# Grupa2_sema.net
KiCad netlist of a schematic drawn in Altium Designer
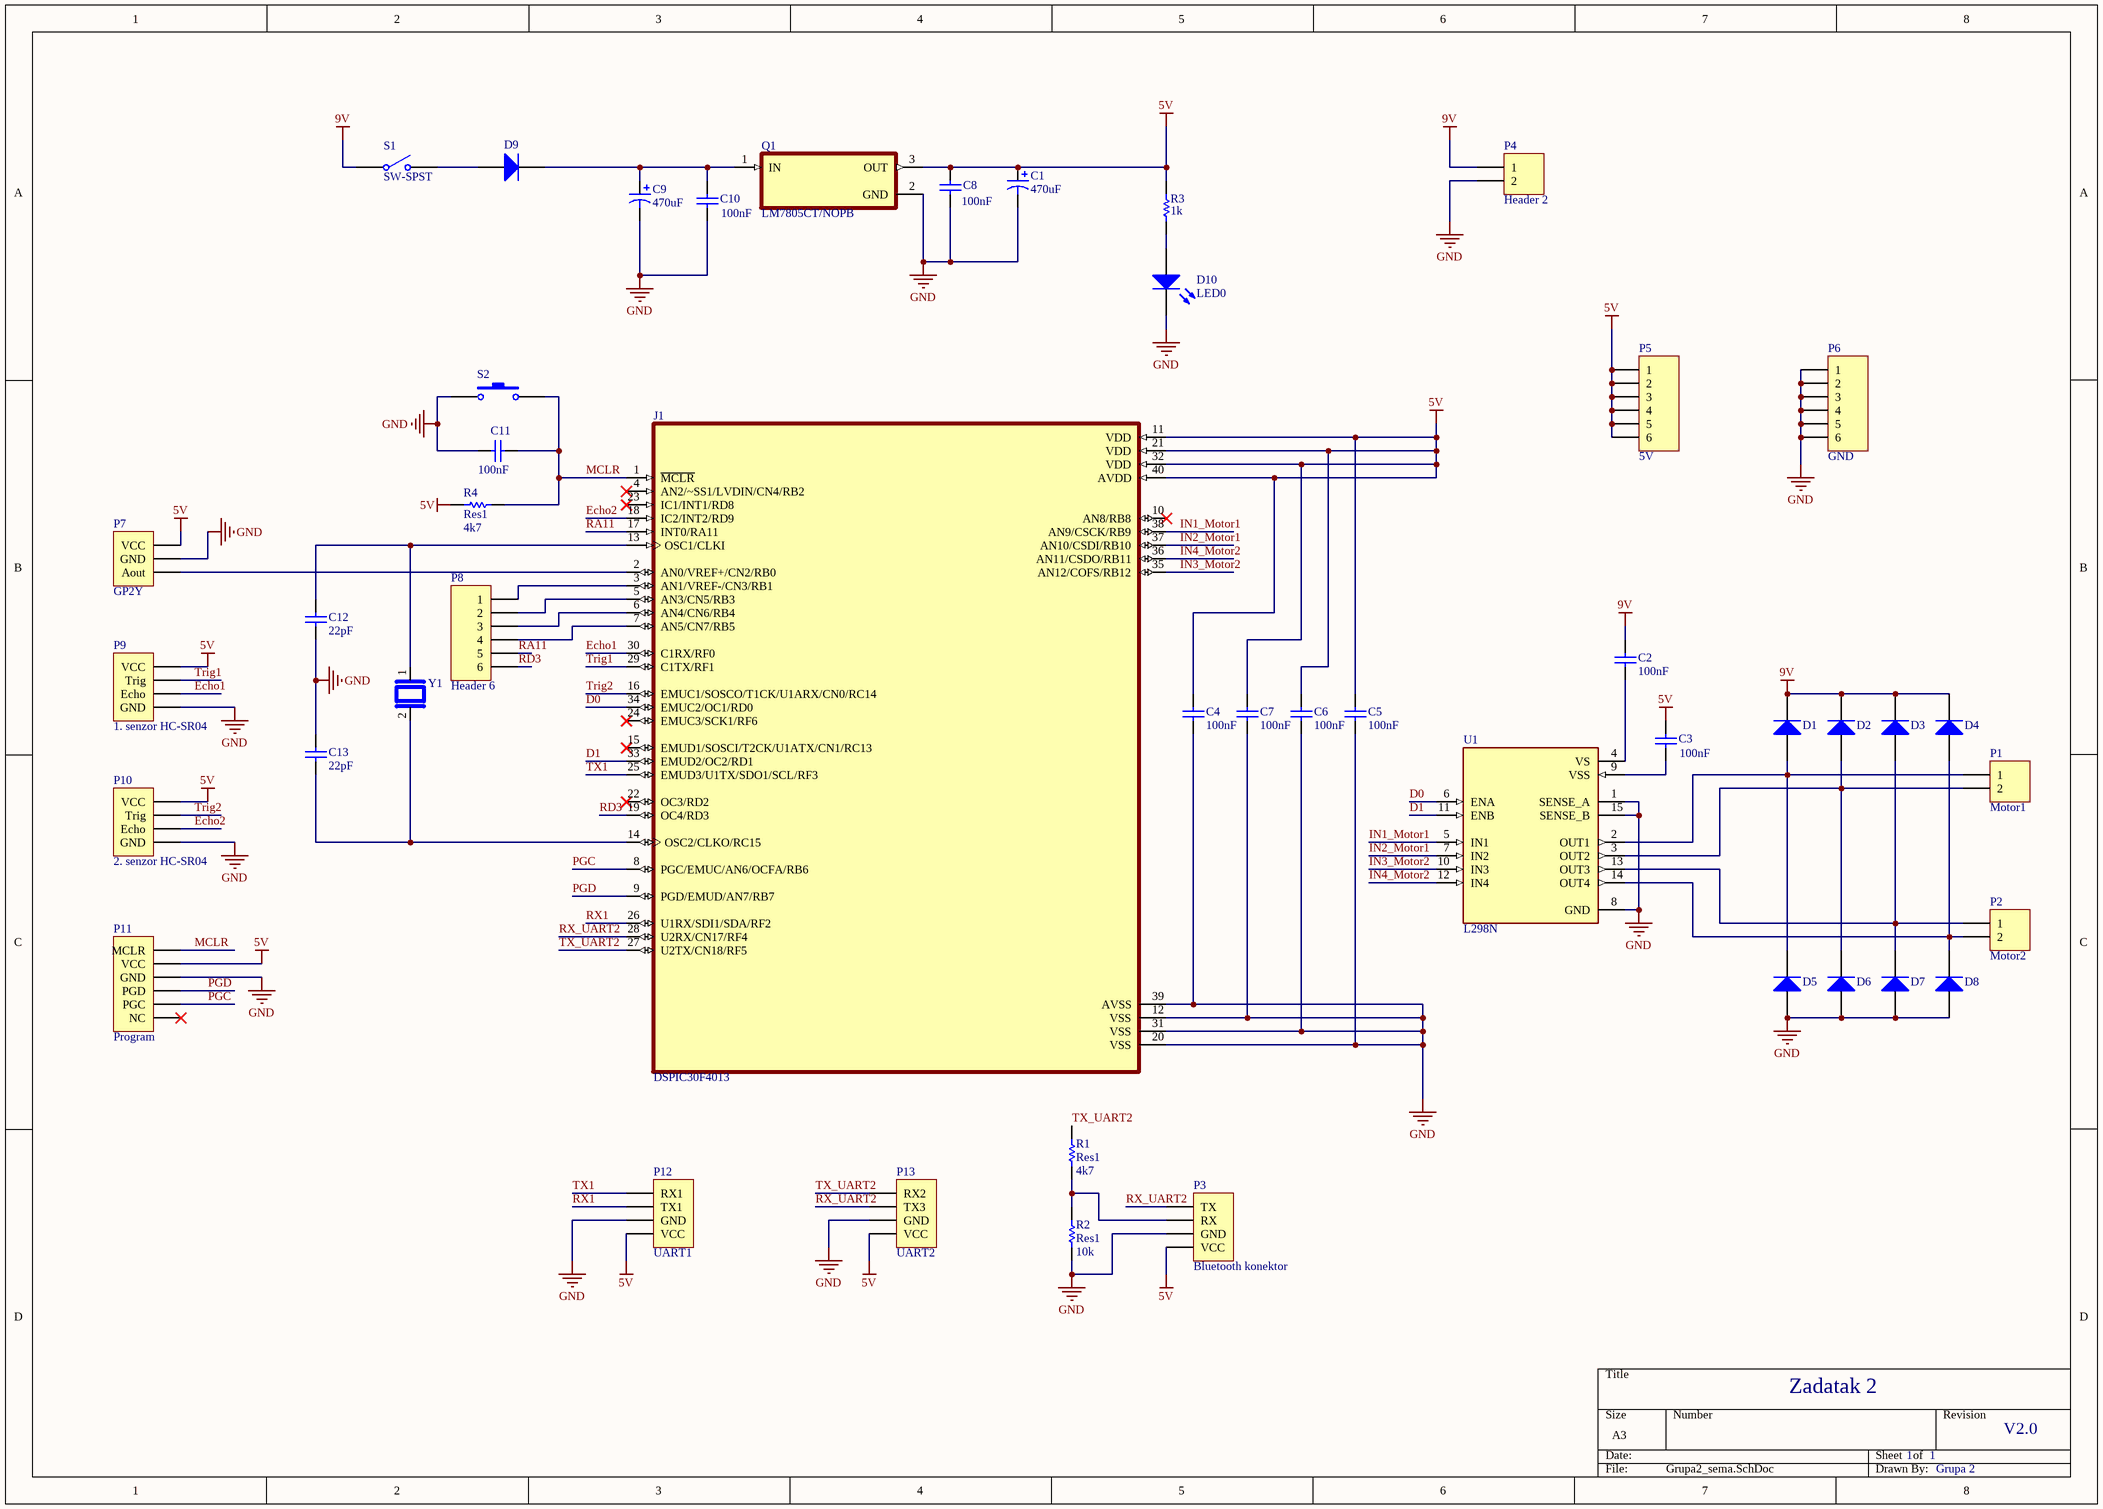
[diagram p0: Grupa2_sema.SchDoc]

(export (version "E")
  (design (tool "Eeschema 10.0.6"))
  (components
    (comp (ref "C1")
      (value "470uF")
      (footprint "elektrolitski kondenzator")
      (description "Polarized Capacitor (Radial)")
      (fields (field (name "Comment") "Cap Pol1") (field (name "PUBLISHER") "Altium Limited"))
      (libsource (lib "Miscellaneous Devices") (part "Cap Pol1"))
    )
    (comp (ref "C2")
      (value "100nF")
      (footprint "RAD-0.1")
      (description "Capacitor")
      (fields (field (name "Comment") "Cap") (field (name "PUBLISHER") "Altium Limited"))
      (libsource (lib "Miscellaneous Devices") (part "Cap"))
    )
    (comp (ref "C3")
      (value "100nF")
      (footprint "RAD-0.1")
      (description "Capacitor")
      (fields (field (name "Comment") "Cap") (field (name "PUBLISHER") "Altium Limited"))
      (libsource (lib "Miscellaneous Devices") (part "Cap"))
    )
    (comp (ref "C4")
      (value "100nF")
      (footprint "RAD-0.1")
      (description "Capacitor")
      (fields (field (name "Comment") "Cap") (field (name "PUBLISHER") "Altium Limited"))
      (libsource (lib "Miscellaneous Devices") (part "Cap"))
    )
    (comp (ref "C5")
      (value "100nF")
      (footprint "RAD-0.1")
      (description "Capacitor")
      (fields (field (name "Comment") "Cap") (field (name "PUBLISHER") "Altium Limited"))
      (libsource (lib "Miscellaneous Devices") (part "Cap"))
    )
    (comp (ref "C6")
      (value "100nF")
      (footprint "RAD-0.1")
      (description "Capacitor")
      (fields (field (name "Comment") "Cap") (field (name "PUBLISHER") "Altium Limited"))
      (libsource (lib "Miscellaneous Devices") (part "Cap"))
    )
    (comp (ref "C7")
      (value "100nF")
      (footprint "RAD-0.1")
      (description "Capacitor")
      (fields (field (name "Comment") "Cap") (field (name "PUBLISHER") "Altium Limited"))
      (libsource (lib "Miscellaneous Devices") (part "Cap"))
    )
    (comp (ref "C8")
      (value "100nF")
      (footprint "RAD-0.1")
      (description "Capacitor")
      (fields (field (name "Comment") "Cap") (field (name "PUBLISHER") "Altium Limited"))
      (libsource (lib "Miscellaneous Devices") (part "Cap"))
    )
    (comp (ref "C9")
      (value "470uF")
      (footprint "elektrolitski kondenzator")
      (description "Polarized Capacitor (Radial)")
      (fields (field (name "Comment") "Cap Pol1") (field (name "PUBLISHER") "Altium Limited"))
      (libsource (lib "Miscellaneous Devices") (part "Cap Pol1"))
    )
    (comp (ref "C10")
      (value "100nF")
      (footprint "RAD-0.1")
      (description "Capacitor")
      (fields (field (name "Comment") "Cap") (field (name "PUBLISHER") "Altium Limited"))
      (libsource (lib "Miscellaneous Devices") (part "Cap"))
    )
    (comp (ref "C11")
      (value "100nF")
      (footprint "RAD-0.1")
      (description "Capacitor")
      (fields (field (name "Comment") "Cap") (field (name "PUBLISHER") "Altium Limited"))
      (libsource (lib "Miscellaneous Devices") (part "Cap"))
    )
    (comp (ref "C12")
      (value "22pF")
      (footprint "RAD-0.1")
      (description "Capacitor")
      (fields (field (name "Comment") "Cap") (field (name "PUBLISHER") "Altium Limited"))
      (libsource (lib "Miscellaneous Devices") (part "Cap"))
    )
    (comp (ref "C13")
      (value "22pF")
      (footprint "RAD-0.1")
      (description "Capacitor")
      (fields (field (name "Comment") "Cap") (field (name "PUBLISHER") "Altium Limited"))
      (libsource (lib "Miscellaneous Devices") (part "Cap"))
    )
    (comp (ref "D1")
      (value "Diode 1N4001")
      (footprint "DO-41")
      (description "1 Amp General Purpose Rectifier")
      (fields (field (name "PUBLISHER") "Altium Limited"))
      (libsource (lib "Miscellaneous Devices") (part "Diode 1N4001"))
    )
    (comp (ref "D2")
      (value "Diode 1N4001")
      (footprint "DO-41")
      (description "1 Amp General Purpose Rectifier")
      (fields (field (name "PUBLISHER") "Altium Limited"))
      (libsource (lib "Miscellaneous Devices") (part "Diode 1N4001"))
    )
    (comp (ref "D3")
      (value "Diode 1N4001")
      (footprint "DO-41")
      (description "1 Amp General Purpose Rectifier")
      (fields (field (name "PUBLISHER") "Altium Limited"))
      (libsource (lib "Miscellaneous Devices") (part "Diode 1N4001"))
    )
    (comp (ref "D4")
      (value "Diode 1N4001")
      (footprint "DO-41")
      (description "1 Amp General Purpose Rectifier")
      (fields (field (name "PUBLISHER") "Altium Limited"))
      (libsource (lib "Miscellaneous Devices") (part "Diode 1N4001"))
    )
    (comp (ref "D5")
      (value "Diode 1N4001")
      (footprint "DO-41")
      (description "1 Amp General Purpose Rectifier")
      (fields (field (name "PUBLISHER") "Altium Limited"))
      (libsource (lib "Miscellaneous Devices") (part "Diode 1N4001"))
    )
    (comp (ref "D6")
      (value "Diode 1N4001")
      (footprint "DO-41")
      (description "1 Amp General Purpose Rectifier")
      (fields (field (name "PUBLISHER") "Altium Limited"))
      (libsource (lib "Miscellaneous Devices") (part "Diode 1N4001"))
    )
    (comp (ref "D7")
      (value "Diode 1N4001")
      (footprint "DO-41")
      (description "1 Amp General Purpose Rectifier")
      (fields (field (name "PUBLISHER") "Altium Limited"))
      (libsource (lib "Miscellaneous Devices") (part "Diode 1N4001"))
    )
    (comp (ref "D8")
      (value "Diode 1N4001")
      (footprint "DO-41")
      (description "1 Amp General Purpose Rectifier")
      (fields (field (name "PUBLISHER") "Altium Limited"))
      (libsource (lib "Miscellaneous Devices") (part "Diode 1N4001"))
    )
    (comp (ref "D9")
      (value "Diode 1N4001")
      (footprint "DO-41")
      (description "1 Amp General Purpose Rectifier")
      (fields (field (name "PUBLISHER") "Altium Limited"))
      (libsource (lib "Miscellaneous Devices") (part "Diode 1N4001"))
    )
    (comp (ref "D10")
      (value "LED0")
      (footprint "LED dioda")
      (description "Typical INFRARED GaAs LED")
      (fields (field (name "PUBLISHER") "Altium Limited"))
      (libsource (lib "Miscellaneous Devices") (part "LED0"))
    )
    (comp (ref "J1")
      (value "DSPIC30F4013")
      (footprint "PDIP40_600MC_MCH")
      (description "Digital Signal Processors, DSP, DSC General Purpose ¦ Microchip Technology Inc. DSPIC30F4013-30I/P")
      (fields (field (name "MF") "Microchip") (field (name "MP") "DSPIC30F4013-30I/P"))
      (libsource (lib "DSPIC30F4013-30I_P") (part "DSPIC30F4013-30I/P"))
    )
    (comp (ref "P1")
      (value "Motor1")
      (footprint "HDR1X2")
      (description "Header, 2-Pin")
      (fields (field (name "PUBLISHER") "Altium Limited"))
      (libsource (lib "Miscellaneous Connectors") (part "Header 2"))
    )
    (comp (ref "P2")
      (value "Motor2")
      (footprint "HDR1X2")
      (description "Header, 2-Pin")
      (fields (field (name "PUBLISHER") "Altium Limited"))
      (libsource (lib "Miscellaneous Connectors") (part "Header 2"))
    )
    (comp (ref "P3")
      (value "Bluetooth konektor")
      (footprint "HDR1X4")
      (description "Header, 4-Pin, Right Angle")
      (fields (field (name "PUBLISHER") "Altium Limited"))
      (libsource (lib "Miscellaneous Connectors") (part "Header 4H"))
    )
    (comp (ref "P4")
      (value "Header 2")
      (footprint "HDR1X2")
      (description "Header, 2-Pin")
      (fields (field (name "PUBLISHER") "Altium Limited"))
      (libsource (lib "Miscellaneous Connectors") (part "Header 2"))
    )
    (comp (ref "P5")
      (value "5V")
      (footprint "HDR1X6")
      (description "Header, 6-Pin")
      (fields (field (name "PUBLISHER") "Altium Limited"))
      (libsource (lib "") (part "Header 6_2"))
    )
    (comp (ref "P6")
      (value "GND")
      (footprint "HDR1X6")
      (description "Header, 6-Pin")
      (fields (field (name "PUBLISHER") "Altium Limited"))
      (libsource (lib "") (part "Header 6_2"))
    )
    (comp (ref "P7")
      (value "GP2Y")
      (footprint "HDR1X3")
      (description "Header, 3-Pin")
      (fields (field (name "PUBLISHER") "Altium Limited"))
      (libsource (lib "Miscellaneous Connectors") (part "Header 3"))
    )
    (comp (ref "P8")
      (value "Header 6")
      (footprint "HDR1X6")
      (description "Header, 6-Pin")
      (fields (field (name "PUBLISHER") "Altium Limited"))
      (libsource (lib "Miscellaneous Connectors") (part "Header 6"))
    )
    (comp (ref "P9")
      (value "1. senzor HC-SR04")
      (footprint "HDR1X4")
      (description "Header, 4-Pin")
      (fields (field (name "PUBLISHER") "Altium Limited"))
      (libsource (lib "Miscellaneous Connectors") (part "Header 4"))
    )
    (comp (ref "P10")
      (value "2. senzor HC-SR04")
      (footprint "HDR1X4")
      (description "Header, 4-Pin")
      (fields (field (name "PUBLISHER") "Altium Limited"))
      (libsource (lib "Miscellaneous Connectors") (part "Header 4"))
    )
    (comp (ref "P11")
      (value "Program")
      (footprint "HDR1X6")
      (description "Header, 6-Pin")
      (fields (field (name "PUBLISHER") "Altium Limited"))
      (libsource (lib "") (part "Header 6_1"))
    )
    (comp (ref "P12")
      (value "UART1")
      (footprint "HDR1X4")
      (description "Header, 4-Pin, Right Angle")
      (fields (field (name "PUBLISHER") "Altium Limited"))
      (libsource (lib "Miscellaneous Connectors") (part "Header 4H"))
    )
    (comp (ref "P13")
      (value "UART2")
      (footprint "HDR1X4")
      (description "Header, 4-Pin, Right Angle")
      (fields (field (name "PUBLISHER") "Altium Limited"))
      (libsource (lib "Miscellaneous Connectors") (part "Header 4H"))
    )
    (comp (ref "Q1")
      (value "LM7805CT/NOPB")
      (footprint "TO254P1054X470X1955-3")
      (fields (field (name "MF") "{'manufacturer': u'Texas Instruments'}"))
      (libsource (lib "LM7805CT_NOPB") (part "LM7805CT/NOPB"))
    )
    (comp (ref "R1")
      (value "Res1")
      (footprint "AXIAL-0.3")
      (description "Resistor")
      (fields (field (name "ALTIUM_VALUE") "4k7") (field (name "PUBLISHER") "Altium Limited"))
      (libsource (lib "Miscellaneous Devices") (part "Res1"))
    )
    (comp (ref "R2")
      (value "Res1")
      (footprint "AXIAL-0.3")
      (description "Resistor")
      (fields (field (name "ALTIUM_VALUE") "10k") (field (name "PUBLISHER") "Altium Limited"))
      (libsource (lib "Miscellaneous Devices") (part "Res1"))
    )
    (comp (ref "R3")
      (value "1k")
      (footprint "AXIAL-0.3")
      (description "Resistor")
      (fields (field (name "Comment") "Res1") (field (name "PUBLISHER") "Altium Limited"))
      (libsource (lib "Miscellaneous Devices") (part "Res1"))
    )
    (comp (ref "R4")
      (value "Res1")
      (footprint "AXIAL-0.3")
      (description "Resistor")
      (fields (field (name "ALTIUM_VALUE") "4k7") (field (name "PUBLISHER") "Altium Limited"))
      (libsource (lib "Miscellaneous Devices") (part "Res1"))
    )
    (comp (ref "S1")
      (value "SW-SPST")
      (footprint "SPST-2")
      (description "Single-Pole, Single-Throw Switch")
      (fields (field (name "PUBLISHER") "Altium Limited"))
      (libsource (lib "Miscellaneous Devices") (part "SW-SPST"))
    )
    (comp (ref "S2")
      (value "SW-PB")
      (footprint "SPST-2")
      (description "Switch")
      (fields (field (name "PUBLISHER") "Altium Limited"))
      (libsource (lib "Miscellaneous Devices") (part "SW-PB"))
    )
    (comp (ref "U1")
      (value "L298N")
      (footprint "TO127P2020X500X2100-15")
      (description "Dual Full Bridge Motor Driver 15-Pin(15+Tab) MULTIWATT V Tube")
      (libsource (lib "L298N") (part "L298N"))
    )
    (comp (ref "Y1")
      (value "HC-49/U-S16000000ABJB")
      (footprint "XTAL_HC49P488W43L1150T466H350")
      (description "16 MHz Â±30ppm Crystal 18pF 50 Ohms HC-49/US")
      (fields (field (name "MF") "Citizen Finedevice"))
      (libsource (lib "HC-49_U-S16000000ABJB") (part "HC-49/U-S16000000ABJB"))
    )
  )
  (nets
    (net (code "1") (name "/D0") (class "Default")
      (node (ref "J1") (pin "34") (pinfunction "EMUC2/OC1/RD0_34") (pintype "bidirectional"))
      (node (ref "U1") (pin "6") (pinfunction "ENA_6") (pintype "input"))
    )
    (net (code "2") (name "/D1") (class "Default")
      (node (ref "J1") (pin "33") (pinfunction "EMUD2/OC2/RD1_33") (pintype "bidirectional"))
      (node (ref "U1") (pin "11") (pinfunction "ENB_11") (pintype "input"))
    )
    (net (code "3") (name "/Echo1") (class "Default")
      (node (ref "J1") (pin "30") (pinfunction "C1RX/RF0_30") (pintype "bidirectional"))
      (node (ref "P9") (pin "3") (pinfunction "Echo_3") (pintype "passive"))
    )
    (net (code "4") (name "/Echo2") (class "Default")
      (node (ref "J1") (pin "18") (pinfunction "IC2/INT2/RD9_18") (pintype "input"))
      (node (ref "P10") (pin "3") (pinfunction "Echo_3") (pintype "passive"))
    )
    (net (code "5") (name "/IN1_Motor1") (class "Default")
      (node (ref "J1") (pin "38") (pinfunction "AN9/CSCK/RB9_38") (pintype "bidirectional"))
      (node (ref "U1") (pin "5") (pinfunction "IN1_5") (pintype "input"))
    )
    (net (code "6") (name "/IN2_Motor1") (class "Default")
      (node (ref "J1") (pin "37") (pinfunction "AN10/CSDI/RB10_37") (pintype "bidirectional"))
      (node (ref "U1") (pin "7") (pinfunction "IN2_7") (pintype "input"))
    )
    (net (code "7") (name "/IN3_Motor2") (class "Default")
      (node (ref "J1") (pin "35") (pinfunction "AN12/COFS/RB12_35") (pintype "bidirectional"))
      (node (ref "U1") (pin "10") (pinfunction "IN3_10") (pintype "input"))
    )
    (net (code "8") (name "/IN4_Motor2") (class "Default")
      (node (ref "J1") (pin "36") (pinfunction "AN11/CSDO/RB11_36") (pintype "bidirectional"))
      (node (ref "U1") (pin "12") (pinfunction "IN4_12") (pintype "input"))
    )
    (net (code "9") (name "/MCLR") (class "Default")
      (node (ref "C11") (pin "2") (pinfunction "2_2") (pintype "passive"))
      (node (ref "J1") (pin "1") (pinfunction "~{MCLR}_1") (pintype "input"))
      (node (ref "P11") (pin "1") (pinfunction "MCLR_1") (pintype "passive"))
      (node (ref "R4") (pin "1") (pinfunction "1_1") (pintype "passive"))
      (node (ref "S2") (pin "2") (pinfunction "2_2") (pintype "passive"))
    )
    (net (code "10") (name "/PGC") (class "Default")
      (node (ref "J1") (pin "8") (pinfunction "PGC/EMUC/AN6/OCFA/RB6_8") (pintype "bidirectional"))
      (node (ref "P11") (pin "5") (pinfunction "PGC_5") (pintype "passive"))
    )
    (net (code "11") (name "/PGD") (class "Default")
      (node (ref "J1") (pin "9") (pinfunction "PGD/EMUD/AN7/RB7_9") (pintype "bidirectional"))
      (node (ref "P11") (pin "4") (pinfunction "PGD_4") (pintype "passive"))
    )
    (net (code "12") (name "/RA11") (class "Default")
      (node (ref "J1") (pin "17") (pinfunction "INT0/RA11_17") (pintype "input"))
      (node (ref "P8") (pin "5") (pinfunction "5_5") (pintype "passive"))
    )
    (net (code "13") (name "/RD3") (class "Default")
      (node (ref "J1") (pin "19") (pinfunction "OC4/RD3_19") (pintype "bidirectional"))
      (node (ref "P8") (pin "6") (pinfunction "6_6") (pintype "passive"))
    )
    (net (code "14") (name "/RX1") (class "Default")
      (node (ref "J1") (pin "26") (pinfunction "U1RX/SDI1/SDA/RF2_26") (pintype "bidirectional"))
      (node (ref "P12") (pin "2") (pinfunction "TX1_2") (pintype "passive"))
    )
    (net (code "15") (name "/RX_UART2") (class "Default")
      (node (ref "J1") (pin "28") (pinfunction "U2RX/CN17/RF4_28") (pintype "bidirectional"))
      (node (ref "P13") (pin "2") (pinfunction "TX1_2") (pintype "passive"))
      (node (ref "P3") (pin "1") (pinfunction "RX1_1") (pintype "passive"))
    )
    (net (code "16") (name "/TX1") (class "Default")
      (node (ref "J1") (pin "25") (pinfunction "EMUD3/U1TX/SDO1/SCL/RF3_25") (pintype "bidirectional"))
      (node (ref "P12") (pin "1") (pinfunction "RX1_1") (pintype "passive"))
    )
    (net (code "17") (name "/TX_UART2") (class "Default")
      (node (ref "J1") (pin "27") (pinfunction "U2TX/CN18/RF5_27") (pintype "bidirectional"))
      (node (ref "P13") (pin "1") (pinfunction "RX1_1") (pintype "passive"))
      (node (ref "R1") (pin "2") (pinfunction "2_2") (pintype "passive"))
    )
    (net (code "18") (name "/Trig1") (class "Default")
      (node (ref "J1") (pin "29") (pinfunction "C1TX/RF1_29") (pintype "bidirectional"))
      (node (ref "P9") (pin "2") (pinfunction "Trig_2") (pintype "passive"))
    )
    (net (code "19") (name "/Trig2") (class "Default")
      (node (ref "J1") (pin "16") (pinfunction "EMUC1/SOSCO/T1CK/U1ARX/CN0/RC14_16") (pintype "bidirectional"))
      (node (ref "P10") (pin "2") (pinfunction "Trig_2") (pintype "passive"))
    )
    (net (code "20") (name "5V") (class "Default")
      (node (ref "C1") (pin "1") (pinfunction "1_1") (pintype "passive"))
      (node (ref "C3") (pin "1") (pinfunction "1_1") (pintype "passive"))
      (node (ref "C4") (pin "2") (pinfunction "2_2") (pintype "passive"))
      (node (ref "C5") (pin "2") (pinfunction "2_2") (pintype "passive"))
      (node (ref "C6") (pin "2") (pinfunction "2_2") (pintype "passive"))
      (node (ref "C7") (pin "2") (pinfunction "2_2") (pintype "passive"))
      (node (ref "C8") (pin "2") (pinfunction "2_2") (pintype "passive"))
      (node (ref "J1") (pin "11") (pinfunction "VDD_11") (pintype "input"))
      (node (ref "J1") (pin "21") (pinfunction "VDD_21") (pintype "input"))
      (node (ref "J1") (pin "32") (pinfunction "VDD_32") (pintype "input"))
      (node (ref "J1") (pin "40") (pinfunction "AVDD_40") (pintype "input"))
      (node (ref "P10") (pin "1") (pinfunction "VCC_1") (pintype "passive"))
      (node (ref "P11") (pin "2") (pinfunction "VCC_2") (pintype "passive"))
      (node (ref "P12") (pin "4") (pinfunction "VCC_4") (pintype "passive"))
      (node (ref "P13") (pin "4") (pinfunction "VCC_4") (pintype "passive"))
      (node (ref "P3") (pin "4") (pinfunction "VCC_4") (pintype "passive"))
      (node (ref "P5") (pin "1") (pinfunction "1_1") (pintype "passive"))
      (node (ref "P5") (pin "2") (pinfunction "2_2") (pintype "passive"))
      (node (ref "P5") (pin "3") (pinfunction "3_3") (pintype "passive"))
      (node (ref "P5") (pin "4") (pinfunction "4_4") (pintype "passive"))
      (node (ref "P5") (pin "5") (pinfunction "5_5") (pintype "passive"))
      (node (ref "P5") (pin "6") (pinfunction "6_6") (pintype "passive"))
      (node (ref "P7") (pin "1") (pinfunction "VCC_1") (pintype "passive"))
      (node (ref "P9") (pin "1") (pinfunction "VCC_1") (pintype "passive"))
      (node (ref "Q1") (pin "3") (pinfunction "OUT_3") (pintype "output"))
      (node (ref "R3") (pin "2") (pinfunction "2_2") (pintype "passive"))
      (node (ref "R4") (pin "2") (pinfunction "2_2") (pintype "passive"))
    )
    (net (code "21") (name "9V") (class "Default")
      (node (ref "C2") (pin "2") (pinfunction "2_2") (pintype "passive"))
      (node (ref "D1") (pin "2") (pinfunction "K_2") (pintype "passive"))
      (node (ref "D2") (pin "2") (pinfunction "K_2") (pintype "passive"))
      (node (ref "D3") (pin "2") (pinfunction "K_2") (pintype "passive"))
      (node (ref "D4") (pin "2") (pinfunction "K_2") (pintype "passive"))
      (node (ref "P4") (pin "1") (pinfunction "1_1") (pintype "passive"))
      (node (ref "S1") (pin "1") (pinfunction "COMMON_1") (pintype "passive"))
    )
    (net (code "22") (name "GND") (class "Default")
      (node (ref "C1") (pin "2") (pinfunction "2_2") (pintype "passive"))
      (node (ref "C10") (pin "1") (pinfunction "1_1") (pintype "passive"))
      (node (ref "C11") (pin "1") (pinfunction "1_1") (pintype "passive"))
      (node (ref "C12") (pin "1") (pinfunction "1_1") (pintype "passive"))
      (node (ref "C13") (pin "2") (pinfunction "2_2") (pintype "passive"))
      (node (ref "C4") (pin "1") (pinfunction "1_1") (pintype "passive"))
      (node (ref "C5") (pin "1") (pinfunction "1_1") (pintype "passive"))
      (node (ref "C6") (pin "1") (pinfunction "1_1") (pintype "passive"))
      (node (ref "C7") (pin "1") (pinfunction "1_1") (pintype "passive"))
      (node (ref "C8") (pin "1") (pinfunction "1_1") (pintype "passive"))
      (node (ref "C9") (pin "2") (pinfunction "2_2") (pintype "passive"))
      (node (ref "D10") (pin "2") (pinfunction "K_2") (pintype "passive"))
      (node (ref "D5") (pin "1") (pinfunction "A_1") (pintype "passive"))
      (node (ref "D6") (pin "1") (pinfunction "A_1") (pintype "passive"))
      (node (ref "D7") (pin "1") (pinfunction "A_1") (pintype "passive"))
      (node (ref "D8") (pin "1") (pinfunction "A_1") (pintype "passive"))
      (node (ref "J1") (pin "12") (pinfunction "VSS_12") (pintype "power_in"))
      (node (ref "J1") (pin "20") (pinfunction "VSS_20") (pintype "power_in"))
      (node (ref "J1") (pin "31") (pinfunction "VSS_31") (pintype "power_in"))
      (node (ref "J1") (pin "39") (pinfunction "AVSS_39") (pintype "power_in"))
      (node (ref "P10") (pin "4") (pinfunction "GND_4") (pintype "passive"))
      (node (ref "P11") (pin "3") (pinfunction "GND_3") (pintype "passive"))
      (node (ref "P12") (pin "3") (pinfunction "GND_3") (pintype "passive"))
      (node (ref "P13") (pin "3") (pinfunction "GND_3") (pintype "passive"))
      (node (ref "P3") (pin "3") (pinfunction "GND_3") (pintype "passive"))
      (node (ref "P4") (pin "2") (pinfunction "2_2") (pintype "passive"))
      (node (ref "P6") (pin "1") (pinfunction "1_1") (pintype "passive"))
      (node (ref "P6") (pin "2") (pinfunction "2_2") (pintype "passive"))
      (node (ref "P6") (pin "3") (pinfunction "3_3") (pintype "passive"))
      (node (ref "P6") (pin "4") (pinfunction "4_4") (pintype "passive"))
      (node (ref "P6") (pin "5") (pinfunction "5_5") (pintype "passive"))
      (node (ref "P6") (pin "6") (pinfunction "6_6") (pintype "passive"))
      (node (ref "P7") (pin "2") (pinfunction "GND_2") (pintype "passive"))
      (node (ref "P9") (pin "4") (pinfunction "GND_4") (pintype "passive"))
      (node (ref "Q1") (pin "2") (pinfunction "GND_2") (pintype "power_in"))
      (node (ref "R2") (pin "1") (pinfunction "1_1") (pintype "passive"))
      (node (ref "S2") (pin "1") (pinfunction "1_1") (pintype "passive"))
      (node (ref "U1") (pin "1") (pinfunction "SENSE_A_1") (pintype "passive"))
      (node (ref "U1") (pin "15") (pinfunction "SENSE_B_15") (pintype "passive"))
      (node (ref "U1") (pin "8") (pinfunction "GND_8") (pintype "power_in"))
    )
    (net (code "23") (name "Net-(D1-A)") (class "Default")
      (node (ref "D1") (pin "1") (pinfunction "A_1") (pintype "passive"))
      (node (ref "D5") (pin "2") (pinfunction "K_2") (pintype "passive"))
      (node (ref "P1") (pin "1") (pinfunction "1_1") (pintype "passive"))
      (node (ref "U1") (pin "2") (pinfunction "OUT1_2") (pintype "output"))
    )
    (net (code "24") (name "Net-(D2-A)") (class "Default")
      (node (ref "D2") (pin "1") (pinfunction "A_1") (pintype "passive"))
      (node (ref "D6") (pin "2") (pinfunction "K_2") (pintype "passive"))
      (node (ref "P1") (pin "2") (pinfunction "2_2") (pintype "passive"))
      (node (ref "U1") (pin "3") (pinfunction "OUT2_3") (pintype "output"))
    )
    (net (code "25") (name "Net-(D3-A)") (class "Default")
      (node (ref "D3") (pin "1") (pinfunction "A_1") (pintype "passive"))
      (node (ref "D7") (pin "2") (pinfunction "K_2") (pintype "passive"))
      (node (ref "P2") (pin "1") (pinfunction "1_1") (pintype "passive"))
      (node (ref "U1") (pin "13") (pinfunction "OUT3_13") (pintype "output"))
    )
    (net (code "26") (name "Net-(D4-A)") (class "Default")
      (node (ref "D4") (pin "1") (pinfunction "A_1") (pintype "passive"))
      (node (ref "D8") (pin "2") (pinfunction "K_2") (pintype "passive"))
      (node (ref "P2") (pin "2") (pinfunction "2_2") (pintype "passive"))
      (node (ref "U1") (pin "14") (pinfunction "OUT4_14") (pintype "output"))
    )
    (net (code "27") (name "Net-(D9-A)") (class "Default")
      (node (ref "D9") (pin "1") (pinfunction "A_1") (pintype "passive"))
      (node (ref "S1") (pin "2") (pinfunction "NO_2") (pintype "passive"))
    )
    (net (code "28") (name "Net-(D9-K)") (class "Default")
      (node (ref "C10") (pin "2") (pinfunction "2_2") (pintype "passive"))
      (node (ref "C9") (pin "1") (pinfunction "1_1") (pintype "passive"))
      (node (ref "D9") (pin "2") (pinfunction "K_2") (pintype "passive"))
      (node (ref "Q1") (pin "1") (pinfunction "IN_1") (pintype "input"))
    )
    (net (code "29") (name "Net-(D10-A)") (class "Default")
      (node (ref "D10") (pin "1") (pinfunction "A_1") (pintype "passive"))
      (node (ref "R3") (pin "1") (pinfunction "1_1") (pintype "passive"))
    )
    (net (code "30") (name "Net-(J1-AN0{slash}VREF+{slash}CN2{slash}RB0)") (class "Default")
      (node (ref "J1") (pin "2") (pinfunction "AN0/VREF+/CN2/RB0_2") (pintype "bidirectional"))
      (node (ref "P7") (pin "3") (pinfunction "Aout_3") (pintype "passive"))
    )
    (net (code "31") (name "Net-(J1-AN1{slash}VREF-{slash}CN3{slash}RB1)") (class "Default")
      (node (ref "J1") (pin "3") (pinfunction "AN1/VREF-/CN3/RB1_3") (pintype "bidirectional"))
      (node (ref "P8") (pin "1") (pinfunction "1_1") (pintype "passive"))
    )
    (net (code "32") (name "Net-(J1-AN3{slash}CN5{slash}RB3)") (class "Default")
      (node (ref "J1") (pin "5") (pinfunction "AN3/CN5/RB3_5") (pintype "bidirectional"))
      (node (ref "P8") (pin "2") (pinfunction "2_2") (pintype "passive"))
    )
    (net (code "33") (name "Net-(J1-AN4{slash}CN6{slash}RB4)") (class "Default")
      (node (ref "J1") (pin "6") (pinfunction "AN4/CN6/RB4_6") (pintype "bidirectional"))
      (node (ref "P8") (pin "3") (pinfunction "3_3") (pintype "passive"))
    )
    (net (code "34") (name "Net-(J1-AN5{slash}CN7{slash}RB5)") (class "Default")
      (node (ref "J1") (pin "7") (pinfunction "AN5/CN7/RB5_7") (pintype "bidirectional"))
      (node (ref "P8") (pin "4") (pinfunction "4_4") (pintype "passive"))
    )
    (net (code "35") (name "Net-(J1-OSC1{slash}CLKI)") (class "Default")
      (node (ref "C12") (pin "2") (pinfunction "2_2") (pintype "passive"))
      (node (ref "J1") (pin "13") (pinfunction "OSC1/CLKI_13") (pintype "input"))
      (node (ref "Y1") (pin "1") (pinfunction "1_1") (pintype "passive"))
    )
    (net (code "36") (name "Net-(J1-OSC2{slash}CLKO{slash}RC15)") (class "Default")
      (node (ref "C13") (pin "1") (pinfunction "1_1") (pintype "passive"))
      (node (ref "J1") (pin "14") (pinfunction "OSC2/CLKO/RC15_14") (pintype "bidirectional"))
      (node (ref "Y1") (pin "2") (pinfunction "2_2") (pintype "passive"))
    )
    (net (code "37") (name "Net-(P3-TX1)") (class "Default")
      (node (ref "P3") (pin "2") (pinfunction "TX1_2") (pintype "passive"))
      (node (ref "R1") (pin "1") (pinfunction "1_1") (pintype "passive"))
      (node (ref "R2") (pin "2") (pinfunction "2_2") (pintype "passive"))
    )
    (net (code "38") (name "Net-(U1-VS)") (class "Default")
      (node (ref "C2") (pin "1") (pinfunction "1_1") (pintype "passive"))
      (node (ref "U1") (pin "4") (pinfunction "VS_4") (pintype "power_in"))
    )
    (net (code "39") (name "Net-(U1-VSS)") (class "Default")
      (node (ref "C3") (pin "2") (pinfunction "2_2") (pintype "passive"))
      (node (ref "U1") (pin "9") (pinfunction "VSS_9") (pintype "input"))
    )
    (net (code "40") (name "unconnected-(J1-AN2{slash}~SS1{slash}LVDIN{slash}CN4{slash}RB2-Pad4)") (class "Default")
      (node (ref "J1") (pin "4") (pinfunction "AN2/~SS1/LVDIN/CN4/RB2_4") (pintype "input+no_connect"))
    )
    (net (code "41") (name "unconnected-(J1-AN8{slash}RB8-Pad10)") (class "Default")
      (node (ref "J1") (pin "10") (pinfunction "AN8/RB8_10") (pintype "bidirectional+no_connect"))
    )
    (net (code "42") (name "unconnected-(J1-EMUC3{slash}SCK1{slash}RF6-Pad24)") (class "Default")
      (node (ref "J1") (pin "24") (pinfunction "EMUC3/SCK1/RF6_24") (pintype "bidirectional+no_connect"))
    )
    (net (code "43") (name "unconnected-(J1-EMUD1{slash}SOSCI{slash}T2CK{slash}U1ATX{slash}CN1{slash}RC13-Pad15)") (class "Default")
      (node (ref "J1") (pin "15") (pinfunction "EMUD1/SOSCI/T2CK/U1ATX/CN1/RC13_15") (pintype "bidirectional+no_connect"))
    )
    (net (code "44") (name "unconnected-(J1-IC1{slash}INT1{slash}RD8-Pad23)") (class "Default")
      (node (ref "J1") (pin "23") (pinfunction "IC1/INT1/RD8_23") (pintype "input+no_connect"))
    )
    (net (code "45") (name "unconnected-(J1-OC3{slash}RD2-Pad22)") (class "Default")
      (node (ref "J1") (pin "22") (pinfunction "OC3/RD2_22") (pintype "bidirectional+no_connect"))
    )
    (net (code "46") (name "unconnected-(P11-NC-Pad6)") (class "Default")
      (node (ref "P11") (pin "6") (pinfunction "NC_6") (pintype "passive+no_connect"))
    )
  )
)
